# T01_Synth_Glove_v4.net
KiCad netlist of a schematic drawn in EAGLE
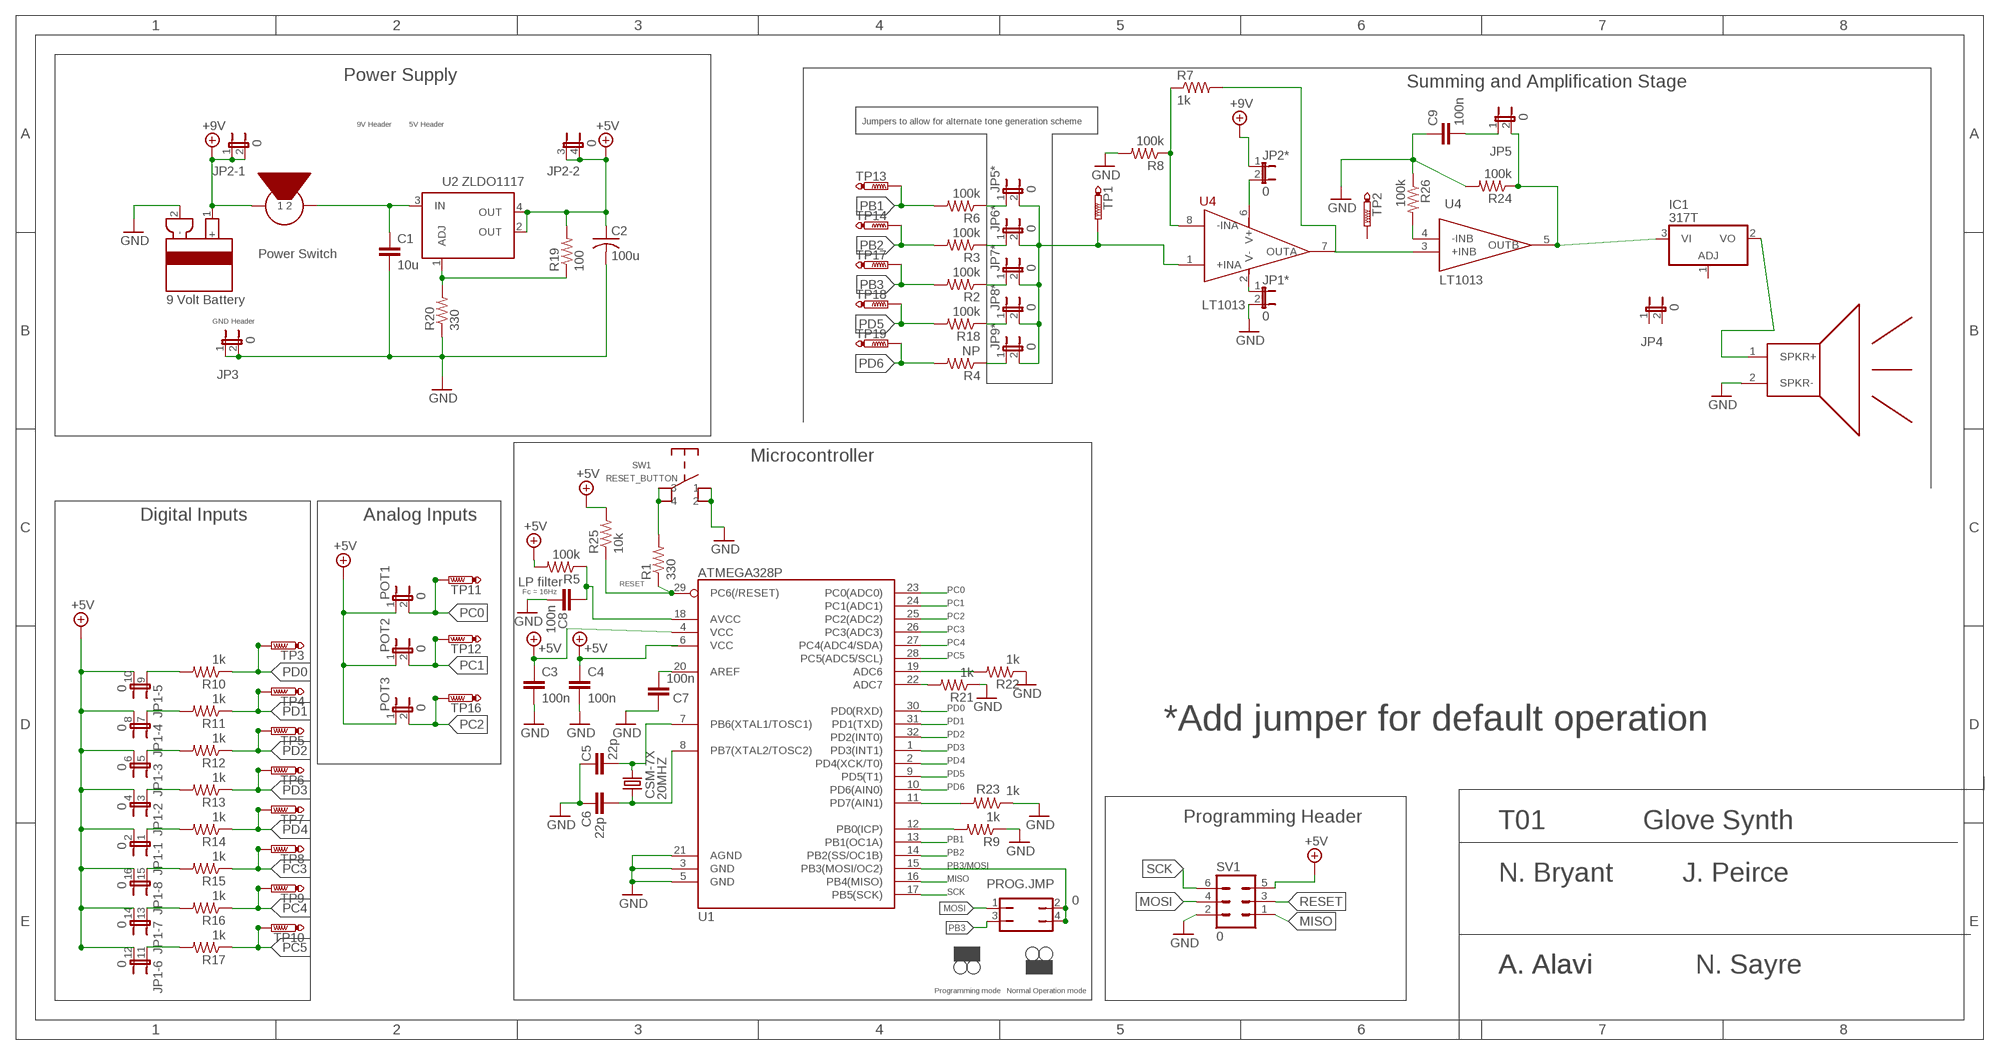
[diagram p0: schematic, sheet 1]

(export (version "E")
  (design (tool "Eeschema 10.0.6"))
  (components
    (comp (ref "20MHZ")
      (value "CSM-7X")
      (footprint "eagle-import:CSM-7X-DU")
      (libsource (lib "eagle-import") (part "CSM-7X-DU"))
    )
    (comp (ref "C1")
      (value "10u")
      (footprint "eagle-import:0603-CAP")
      (libsource (lib "eagle-import") (part "CAP0603-CAP"))
    )
    (comp (ref "C2")
      (value "100u")
      (footprint "eagle-import:C075-042X103")
      (libsource (lib "eagle-import") (part "C-US075-042X103"))
    )
    (comp (ref "C3")
      (value "100n")
      (footprint "eagle-import:0603-CAP")
      (libsource (lib "eagle-import") (part "CAP0603-CAP"))
    )
    (comp (ref "C4")
      (value "100n")
      (footprint "eagle-import:0603-CAP")
      (libsource (lib "eagle-import") (part "CAP0603-CAP"))
    )
    (comp (ref "C5")
      (value "22p")
      (footprint "eagle-import:0603-CAP")
      (libsource (lib "eagle-import") (part "CAP0603-CAP"))
    )
    (comp (ref "C6")
      (value "22p")
      (footprint "eagle-import:0603-CAP")
      (libsource (lib "eagle-import") (part "CAP0603-CAP"))
    )
    (comp (ref "C7")
      (value "100n")
      (footprint "eagle-import:0603-CAP")
      (libsource (lib "eagle-import") (part "CAP0603-CAP"))
    )
    (comp (ref "C8")
      (value "100n")
      (footprint "eagle-import:0603-CAP")
      (libsource (lib "eagle-import") (part "CAP0603-CAP"))
    )
    (comp (ref "C9")
      (value "100n")
      (footprint "eagle-import:0603-CAP")
      (libsource (lib "eagle-import") (part "CAP0603-CAP"))
    )
    (comp (ref "IC1")
      (value "317T")
      (footprint "eagle-import:TO220H")
      (libsource (lib "eagle-import") (part "317T"))
    )
    (comp (ref "JP1")
      (value "0")
      (footprint "eagle-import:JP8Q")
      (libsource (lib "eagle-import") (part "JP8QE"))
    )
    (comp (ref "JP1*")
      (value "0")
      (footprint "eagle-import:JP1")
      (libsource (lib "eagle-import") (part "JP1E"))
    )
    (comp (ref "JP2")
      (value "0")
      (footprint "eagle-import:JP2Q")
      (libsource (lib "eagle-import") (part "JP2QE"))
    )
    (comp (ref "JP2*")
      (value "0")
      (footprint "eagle-import:JP1")
      (libsource (lib "eagle-import") (part "JP1E"))
    )
    (comp (ref "JP3")
      (value "0")
      (footprint "eagle-import:JP1")
      (libsource (lib "eagle-import") (part "JP1E"))
    )
    (comp (ref "JP4")
      (value "0")
      (footprint "eagle-import:JP1")
      (libsource (lib "eagle-import") (part "JP1E"))
    )
    (comp (ref "JP5")
      (value "0")
      (footprint "eagle-import:JP1")
      (libsource (lib "eagle-import") (part "JP1E"))
    )
    (comp (ref "JP5*")
      (value "0")
      (footprint "eagle-import:JP1")
      (libsource (lib "eagle-import") (part "JP1E"))
    )
    (comp (ref "JP6*")
      (value "0")
      (footprint "eagle-import:JP1")
      (libsource (lib "eagle-import") (part "JP1E"))
    )
    (comp (ref "JP7*")
      (value "0")
      (footprint "eagle-import:JP1")
      (libsource (lib "eagle-import") (part "JP1E"))
    )
    (comp (ref "JP8*")
      (value "0")
      (footprint "eagle-import:JP1")
      (libsource (lib "eagle-import") (part "JP1E"))
    )
    (comp (ref "JP9*")
      (value "0")
      (footprint "eagle-import:JP1")
      (libsource (lib "eagle-import") (part "JP1E"))
    )
    (comp (ref "POT1")
      (value "0")
      (footprint "eagle-import:JP1")
      (libsource (lib "eagle-import") (part "JP1E"))
    )
    (comp (ref "POT2")
      (value "0")
      (footprint "eagle-import:JP1")
      (libsource (lib "eagle-import") (part "JP1E"))
    )
    (comp (ref "POT3")
      (value "0")
      (footprint "eagle-import:JP1")
      (libsource (lib "eagle-import") (part "JP1E"))
    )
    (comp (ref "PROG.JMP")
      (value "0")
      (footprint "eagle-import:JP2Q")
      (libsource (lib "eagle-import") (part "JP2Q"))
    )
    (comp (ref "R1")
      (value "330")
      (footprint "eagle-import:0603-RES")
      (libsource (lib "eagle-import") (part "RESISTOR0603"))
    )
    (comp (ref "R2")
      (value "100k")
      (footprint "eagle-import:0603-RES")
      (libsource (lib "eagle-import") (part "RESISTOR0603"))
    )
    (comp (ref "R3")
      (value "100k")
      (footprint "eagle-import:0603-RES")
      (libsource (lib "eagle-import") (part "RESISTOR0603"))
    )
    (comp (ref "R4")
      (value "NP")
      (footprint "eagle-import:0603-RES")
      (libsource (lib "eagle-import") (part "RESISTOR0603"))
    )
    (comp (ref "R5")
      (value "100k")
      (footprint "eagle-import:0603-RES")
      (libsource (lib "eagle-import") (part "RESISTOR0603"))
    )
    (comp (ref "R6")
      (value "100k")
      (footprint "eagle-import:0603-RES")
      (libsource (lib "eagle-import") (part "RESISTOR0603"))
    )
    (comp (ref "R7")
      (value "1k")
      (footprint "eagle-import:0603-RES")
      (libsource (lib "eagle-import") (part "RESISTOR0603"))
    )
    (comp (ref "R8")
      (value "100k")
      (footprint "eagle-import:0603-RES")
      (libsource (lib "eagle-import") (part "RESISTOR0603"))
    )
    (comp (ref "R9")
      (value "1k")
      (footprint "eagle-import:0603-RES")
      (libsource (lib "eagle-import") (part "RESISTOR0603"))
    )
    (comp (ref "R10")
      (value "1k")
      (footprint "eagle-import:0603-RES")
      (libsource (lib "eagle-import") (part "RESISTOR0603"))
    )
    (comp (ref "R11")
      (value "1k")
      (footprint "eagle-import:0603-RES")
      (libsource (lib "eagle-import") (part "RESISTOR0603"))
    )
    (comp (ref "R12")
      (value "1k")
      (footprint "eagle-import:0603-RES")
      (libsource (lib "eagle-import") (part "RESISTOR0603"))
    )
    (comp (ref "R13")
      (value "1k")
      (footprint "eagle-import:0603-RES")
      (libsource (lib "eagle-import") (part "RESISTOR0603"))
    )
    (comp (ref "R14")
      (value "1k")
      (footprint "eagle-import:0603-RES")
      (libsource (lib "eagle-import") (part "RESISTOR0603"))
    )
    (comp (ref "R15")
      (value "1k")
      (footprint "eagle-import:0603-RES")
      (libsource (lib "eagle-import") (part "RESISTOR0603"))
    )
    (comp (ref "R16")
      (value "1k")
      (footprint "eagle-import:0603-RES")
      (libsource (lib "eagle-import") (part "RESISTOR0603"))
    )
    (comp (ref "R17")
      (value "1k")
      (footprint "eagle-import:0603-RES")
      (libsource (lib "eagle-import") (part "RESISTOR0603"))
    )
    (comp (ref "R18")
      (value "100k")
      (footprint "eagle-import:0603-RES")
      (libsource (lib "eagle-import") (part "RESISTOR0603"))
    )
    (comp (ref "R19")
      (value "100")
      (footprint "eagle-import:0603-RES")
      (libsource (lib "eagle-import") (part "RESISTOR0603"))
    )
    (comp (ref "R20")
      (value "330")
      (footprint "eagle-import:0603-RES")
      (libsource (lib "eagle-import") (part "RESISTOR0603"))
    )
    (comp (ref "R21")
      (value "1k")
      (footprint "eagle-import:0603-RES")
      (libsource (lib "eagle-import") (part "RESISTOR0603"))
    )
    (comp (ref "R22")
      (value "1k")
      (footprint "eagle-import:0603-RES")
      (libsource (lib "eagle-import") (part "RESISTOR0603"))
    )
    (comp (ref "R23")
      (value "1k")
      (footprint "eagle-import:0603-RES")
      (libsource (lib "eagle-import") (part "RESISTOR0603"))
    )
    (comp (ref "R24")
      (value "100k")
      (footprint "eagle-import:0603-RES")
      (libsource (lib "eagle-import") (part "RESISTOR0603"))
    )
    (comp (ref "R25")
      (value "10k")
      (footprint "eagle-import:0603-RES")
      (libsource (lib "eagle-import") (part "RESISTOR0603"))
    )
    (comp (ref "R26")
      (value "100k")
      (footprint "eagle-import:0603-RES")
      (libsource (lib "eagle-import") (part "RESISTOR0603"))
    )
    (comp (ref "SV1")
      (value "0")
      (footprint "eagle-import:MA03-2")
      (libsource (lib "eagle-import") (part "MA03-2"))
    )
    (comp (ref "SW1")
      (value "RESET_BUTTON")
      (footprint "eagle-import:RESET_BUTTON")
      (libsource (lib "eagle-import") (part "RESET_BUTTON"))
    )
    (comp (ref "TP1")
      (value "PTR1B2,54")
      (footprint "eagle-import:B2,54")
      (libsource (lib "eagle-import") (part "PTR1B2,54"))
    )
    (comp (ref "TP2")
      (value "PTR1B2,54")
      (footprint "eagle-import:B2,54")
      (libsource (lib "eagle-import") (part "PTR1B2,54"))
    )
    (comp (ref "TP3")
      (value "PTR1B2,54")
      (footprint "eagle-import:B2,54")
      (libsource (lib "eagle-import") (part "PTR1B2,54"))
    )
    (comp (ref "TP4")
      (value "PTR1B2,54")
      (footprint "eagle-import:B2,54")
      (libsource (lib "eagle-import") (part "PTR1B2,54"))
    )
    (comp (ref "TP5")
      (value "PTR1B2,54")
      (footprint "eagle-import:B2,54")
      (libsource (lib "eagle-import") (part "PTR1B2,54"))
    )
    (comp (ref "TP6")
      (value "PTR1B2,54")
      (footprint "eagle-import:B2,54")
      (libsource (lib "eagle-import") (part "PTR1B2,54"))
    )
    (comp (ref "TP7")
      (value "PTR1B2,54")
      (footprint "eagle-import:B2,54")
      (libsource (lib "eagle-import") (part "PTR1B2,54"))
    )
    (comp (ref "TP8")
      (value "PTR1B2,54")
      (footprint "eagle-import:B2,54")
      (libsource (lib "eagle-import") (part "PTR1B2,54"))
    )
    (comp (ref "TP9")
      (value "PTR1B2,54")
      (footprint "eagle-import:B2,54")
      (libsource (lib "eagle-import") (part "PTR1B2,54"))
    )
    (comp (ref "TP10")
      (value "PTR1B2,54")
      (footprint "eagle-import:B2,54")
      (libsource (lib "eagle-import") (part "PTR1B2,54"))
    )
    (comp (ref "TP11")
      (value "PTR1B2,54")
      (footprint "eagle-import:B2,54")
      (libsource (lib "eagle-import") (part "PTR1B2,54"))
    )
    (comp (ref "TP12")
      (value "PTR1B2,54")
      (footprint "eagle-import:B2,54")
      (libsource (lib "eagle-import") (part "PTR1B2,54"))
    )
    (comp (ref "TP13")
      (value "PTR1B2,54")
      (footprint "eagle-import:B2,54")
      (libsource (lib "eagle-import") (part "PTR1B2,54"))
    )
    (comp (ref "TP14")
      (value "PTR1B2,54")
      (footprint "eagle-import:B2,54")
      (libsource (lib "eagle-import") (part "PTR1B2,54"))
    )
    (comp (ref "TP16")
      (value "PTR1B2,54")
      (footprint "eagle-import:B2,54")
      (libsource (lib "eagle-import") (part "PTR1B2,54"))
    )
    (comp (ref "TP17")
      (value "PTR1B2,54")
      (footprint "eagle-import:B2,54")
      (libsource (lib "eagle-import") (part "PTR1B2,54"))
    )
    (comp (ref "TP18")
      (value "PTR1B2,54")
      (footprint "eagle-import:B2,54")
      (libsource (lib "eagle-import") (part "PTR1B2,54"))
    )
    (comp (ref "TP19")
      (value "PTR1B2,54")
      (footprint "eagle-import:B2,54")
      (libsource (lib "eagle-import") (part "PTR1B2,54"))
    )
    (comp (ref "U$1")
      (value "SPEAKER")
      (footprint "eagle-import:JP1")
      (libsource (lib "eagle-import") (part "SPEAKER"))
    )
    (comp (ref "U$7")
      (value "POWER_SWITCH")
      (footprint "eagle-import:JP1")
      (libsource (lib "eagle-import") (part "POWER_SWITCH"))
    )
    (comp (ref "U$8")
      (value "9VOLTBATTERY")
      (footprint "eagle-import:JP1")
      (libsource (lib "eagle-import") (part "9VOLTBATTERY"))
    )
    (comp (ref "U1")
      (value "ATMEGA328P")
      (footprint "eagle-import:TQFP32-08")
      (libsource (lib "eagle-import") (part "ATMEGA328_SMT"))
    )
    (comp (ref "U2")
      (value "ZLDO1117")
      (footprint "eagle-import:SOT223")
      (libsource (lib "eagle-import") (part "ZLDO1117"))
    )
    (comp (ref "U4")
      (value "LT1013")
      (footprint "eagle-import:SO08")
      (libsource (lib "eagle-import") (part "LT1013"))
    )
  )
  (nets
    (net (code "1") (name "+5V") (class "Default")
      (node (ref "C2") (pin "1") (pinfunction "1_1") (pintype "passive"))
      (node (ref "C3") (pin "1") (pinfunction "1_1") (pintype "passive"))
      (node (ref "C4") (pin "1") (pinfunction "1_1") (pintype "passive"))
      (node (ref "JP1") (pin "10") (pinfunction "2_10") (pintype "passive"))
      (node (ref "JP1") (pin "12") (pinfunction "2_12") (pintype "passive"))
      (node (ref "JP1") (pin "14") (pinfunction "2_14") (pintype "passive"))
      (node (ref "JP1") (pin "16") (pinfunction "2_16") (pintype "passive"))
      (node (ref "JP1") (pin "2") (pinfunction "2_2") (pintype "passive"))
      (node (ref "JP1") (pin "4") (pinfunction "2_4") (pintype "passive"))
      (node (ref "JP1") (pin "6") (pinfunction "2_6") (pintype "passive"))
      (node (ref "JP1") (pin "8") (pinfunction "2_8") (pintype "passive"))
      (node (ref "JP2") (pin "3") (pinfunction "1_3") (pintype "passive"))
      (node (ref "JP2") (pin "4") (pinfunction "2_4") (pintype "passive"))
      (node (ref "POT1") (pin "1") (pinfunction "1_1") (pintype "passive"))
      (node (ref "POT2") (pin "1") (pinfunction "1_1") (pintype "passive"))
      (node (ref "POT3") (pin "1") (pinfunction "1_1") (pintype "passive"))
      (node (ref "R19") (pin "2") (pinfunction "2_2") (pintype "passive"))
      (node (ref "R25") (pin "2") (pinfunction "2_2") (pintype "passive"))
      (node (ref "R5") (pin "2") (pinfunction "2_2") (pintype "passive"))
      (node (ref "SV1") (pin "5") (pinfunction "5_5") (pintype "passive"))
      (node (ref "U1") (pin "4") (pinfunction "VCC_4") (pintype "bidirectional"))
      (node (ref "U2") (pin "2") (pinfunction "OUT_2") (pintype "bidirectional"))
      (node (ref "U2") (pin "4") (pinfunction "OUT_4") (pintype "bidirectional"))
    )
    (net (code "2") (name "+9V") (class "Default")
      (node (ref "JP2") (pin "1") (pinfunction "1_1") (pintype "passive"))
      (node (ref "JP2") (pin "2") (pinfunction "2_2") (pintype "passive"))
      (node (ref "JP2*") (pin "1") (pinfunction "1_1") (pintype "passive"))
      (node (ref "U$7") (pin "1") (pinfunction "1_1") (pintype "bidirectional"))
      (node (ref "U$8") (pin "1") (pinfunction "+_1") (pintype "bidirectional"))
    )
    (net (code "3") (name "/PB3{slash}MOSI") (class "Default")
      (node (ref "PROG.JMP") (pin "2") (pinfunction "2_2") (pintype "passive"))
      (node (ref "PROG.JMP") (pin "4") (pinfunction "4_4") (pintype "passive"))
      (node (ref "U1") (pin "15") (pinfunction "PB3(MOSI/OC2)_15") (pintype "bidirectional"))
    )
    (net (code "4") (name "GND") (class "Default")
      (node (ref "C1") (pin "2") (pinfunction "2_2") (pintype "passive"))
      (node (ref "C2") (pin "2") (pinfunction "2_2") (pintype "passive"))
      (node (ref "C3") (pin "2") (pinfunction "2_2") (pintype "passive"))
      (node (ref "C4") (pin "2") (pinfunction "2_2") (pintype "passive"))
      (node (ref "C5") (pin "2") (pinfunction "2_2") (pintype "passive"))
      (node (ref "C6") (pin "2") (pinfunction "2_2") (pintype "passive"))
      (node (ref "C7") (pin "2") (pinfunction "2_2") (pintype "passive"))
      (node (ref "C8") (pin "2") (pinfunction "2_2") (pintype "passive"))
      (node (ref "C9") (pin "1") (pinfunction "1_1") (pintype "passive"))
      (node (ref "JP1*") (pin "2") (pinfunction "2_2") (pintype "passive"))
      (node (ref "JP3") (pin "1") (pinfunction "1_1") (pintype "passive"))
      (node (ref "JP3") (pin "2") (pinfunction "2_2") (pintype "passive"))
      (node (ref "R20") (pin "1") (pinfunction "1_1") (pintype "passive"))
      (node (ref "R21") (pin "1") (pinfunction "1_1") (pintype "passive"))
      (node (ref "R22") (pin "1") (pinfunction "1_1") (pintype "passive"))
      (node (ref "R23") (pin "1") (pinfunction "1_1") (pintype "passive"))
      (node (ref "R24") (pin "2") (pinfunction "2_2") (pintype "passive"))
      (node (ref "R26") (pin "1") (pinfunction "1_1") (pintype "passive"))
      (node (ref "R8") (pin "2") (pinfunction "2_2") (pintype "passive"))
      (node (ref "R9") (pin "1") (pinfunction "1_1") (pintype "passive"))
      (node (ref "SV1") (pin "2") (pinfunction "2_2") (pintype "passive"))
      (node (ref "SW1") (pin "1") (pinfunction "1_1") (pintype "bidirectional"))
      (node (ref "SW1") (pin "2") (pinfunction "2_2") (pintype "bidirectional"))
      (node (ref "U$1") (pin "2") (pinfunction "SPKR-_2") (pintype "bidirectional"))
      (node (ref "U$8") (pin "2") (pinfunction "-_2") (pintype "bidirectional"))
      (node (ref "U1") (pin "21") (pinfunction "AGND_21") (pintype "bidirectional"))
      (node (ref "U1") (pin "3") (pinfunction "GND_3") (pintype "bidirectional"))
      (node (ref "U1") (pin "5") (pinfunction "GND_5") (pintype "bidirectional"))
    )
    (net (code "5") (name "MISO") (class "Default")
      (node (ref "SV1") (pin "1") (pinfunction "1_1") (pintype "passive"))
      (node (ref "U1") (pin "16") (pinfunction "PB4(MISO)_16") (pintype "bidirectional"))
    )
    (net (code "6") (name "MOSI") (class "Default")
      (node (ref "PROG.JMP") (pin "1") (pinfunction "1_1") (pintype "passive"))
      (node (ref "SV1") (pin "4") (pinfunction "4_4") (pintype "passive"))
    )
    (net (code "7") (name "Net-(C9-Pad2)") (class "Default")
      (node (ref "C9") (pin "2") (pinfunction "2_2") (pintype "passive"))
      (node (ref "JP5") (pin "1") (pinfunction "1_1") (pintype "passive"))
    )
    (net (code "8") (name "Net-(IC1-VI)") (class "Default")
      (node (ref "IC1") (pin "3") (pinfunction "VI_3") (pintype "input"))
      (node (ref "JP5") (pin "2") (pinfunction "2_2") (pintype "passive"))
      (node (ref "R24") (pin "1") (pinfunction "1_1") (pintype "passive"))
      (node (ref "U4") (pin "5") (pinfunction "OUTB_5") (pintype "bidirectional"))
    )
    (net (code "9") (name "Net-(JP1-Pad1)") (class "Default")
      (node (ref "JP1") (pin "1") (pinfunction "1_1") (pintype "passive"))
      (node (ref "R14") (pin "2") (pinfunction "2_2") (pintype "passive"))
    )
    (net (code "10") (name "Net-(JP1B-1)") (class "Default")
      (node (ref "JP1") (pin "3") (pinfunction "1_3") (pintype "passive"))
      (node (ref "R13") (pin "2") (pinfunction "2_2") (pintype "passive"))
    )
    (net (code "11") (name "Net-(JP1C-1)") (class "Default")
      (node (ref "JP1") (pin "5") (pinfunction "1_5") (pintype "passive"))
      (node (ref "R12") (pin "2") (pinfunction "2_2") (pintype "passive"))
    )
    (net (code "12") (name "Net-(JP1D-1)") (class "Default")
      (node (ref "JP1") (pin "7") (pinfunction "1_7") (pintype "passive"))
      (node (ref "R11") (pin "2") (pinfunction "2_2") (pintype "passive"))
    )
    (net (code "13") (name "Net-(JP1E-1)") (class "Default")
      (node (ref "JP1") (pin "9") (pinfunction "1_9") (pintype "passive"))
      (node (ref "R10") (pin "2") (pinfunction "2_2") (pintype "passive"))
    )
    (net (code "14") (name "Net-(JP1F-1)") (class "Default")
      (node (ref "JP1") (pin "11") (pinfunction "1_11") (pintype "passive"))
      (node (ref "R17") (pin "2") (pinfunction "2_2") (pintype "passive"))
    )
    (net (code "15") (name "Net-(JP1G-1)") (class "Default")
      (node (ref "JP1") (pin "13") (pinfunction "1_13") (pintype "passive"))
      (node (ref "R16") (pin "2") (pinfunction "2_2") (pintype "passive"))
    )
    (net (code "16") (name "Net-(JP1H-1)") (class "Default")
      (node (ref "JP1") (pin "15") (pinfunction "1_15") (pintype "passive"))
      (node (ref "R15") (pin "2") (pinfunction "2_2") (pintype "passive"))
    )
    (net (code "17") (name "Net-(JP5*-Pad1)") (class "Default")
      (node (ref "JP5*") (pin "1") (pinfunction "1_1") (pintype "passive"))
      (node (ref "R6") (pin "1") (pinfunction "1_1") (pintype "passive"))
    )
    (net (code "18") (name "Net-(JP6*-Pad1)") (class "Default")
      (node (ref "JP6*") (pin "1") (pinfunction "1_1") (pintype "passive"))
      (node (ref "R3") (pin "1") (pinfunction "1_1") (pintype "passive"))
    )
    (net (code "19") (name "Net-(JP7*-Pad1)") (class "Default")
      (node (ref "JP7*") (pin "1") (pinfunction "1_1") (pintype "passive"))
      (node (ref "R2") (pin "1") (pinfunction "1_1") (pintype "passive"))
    )
    (net (code "20") (name "Net-(JP8*-Pad1)") (class "Default")
      (node (ref "JP8*") (pin "1") (pinfunction "1_1") (pintype "passive"))
      (node (ref "R18") (pin "1") (pinfunction "1_1") (pintype "passive"))
    )
    (net (code "21") (name "Net-(JP9*-Pad1)") (class "Default")
      (node (ref "JP9*") (pin "1") (pinfunction "1_1") (pintype "passive"))
      (node (ref "R4") (pin "1") (pinfunction "1_1") (pintype "passive"))
    )
    (net (code "22") (name "Net-(R1-Pad2)") (class "Default")
      (node (ref "R1") (pin "2") (pinfunction "2_2") (pintype "passive"))
      (node (ref "SW1") (pin "3") (pinfunction "3_3") (pintype "bidirectional"))
      (node (ref "SW1") (pin "4") (pinfunction "4_4") (pintype "bidirectional"))
    )
    (net (code "23") (name "Net-(U1-ADC6)") (class "Default")
      (node (ref "R22") (pin "2") (pinfunction "2_2") (pintype "passive"))
      (node (ref "U1") (pin "19") (pinfunction "ADC6_19") (pintype "bidirectional"))
    )
    (net (code "24") (name "Net-(U1-ADC7)") (class "Default")
      (node (ref "R21") (pin "2") (pinfunction "2_2") (pintype "passive"))
      (node (ref "U1") (pin "22") (pinfunction "ADC7_22") (pintype "bidirectional"))
    )
    (net (code "25") (name "Net-(U1-AREF)") (class "Default")
      (node (ref "C7") (pin "1") (pinfunction "1_1") (pintype "passive"))
      (node (ref "U1") (pin "20") (pinfunction "AREF_20") (pintype "bidirectional"))
    )
    (net (code "26") (name "Net-(U1-AVCC)") (class "Default")
      (node (ref "C8") (pin "1") (pinfunction "1_1") (pintype "passive"))
      (node (ref "R5") (pin "1") (pinfunction "1_1") (pintype "passive"))
      (node (ref "U1") (pin "18") (pinfunction "AVCC_18") (pintype "bidirectional"))
    )
    (net (code "27") (name "Net-(U1-PB0(ICP))") (class "Default")
      (node (ref "R9") (pin "2") (pinfunction "2_2") (pintype "passive"))
      (node (ref "U1") (pin "12") (pinfunction "PB0(ICP)_12") (pintype "bidirectional"))
    )
    (net (code "28") (name "Net-(U1-PB6(XTAL1{slash}TOSC1))") (class "Default")
      (node (ref "20MHZ") (pin "1") (pinfunction "1_1") (pintype "passive"))
      (node (ref "C5") (pin "1") (pinfunction "1_1") (pintype "passive"))
      (node (ref "U1") (pin "7") (pinfunction "PB6(XTAL1/TOSC1)_7") (pintype "bidirectional"))
    )
    (net (code "29") (name "Net-(U1-PB7(XTAL2{slash}TOSC2))") (class "Default")
      (node (ref "20MHZ") (pin "2") (pinfunction "2_2") (pintype "passive"))
      (node (ref "C6") (pin "1") (pinfunction "1_1") (pintype "passive"))
      (node (ref "U1") (pin "8") (pinfunction "PB7(XTAL2/TOSC2)_8") (pintype "bidirectional"))
    )
    (net (code "30") (name "Net-(U1-PD7(AIN1))") (class "Default")
      (node (ref "R23") (pin "2") (pinfunction "2_2") (pintype "passive"))
      (node (ref "U1") (pin "11") (pinfunction "PD7(AIN1)_11") (pintype "bidirectional"))
    )
    (net (code "31") (name "Net-(U2-ADJ)") (class "Default")
      (node (ref "R19") (pin "1") (pinfunction "1_1") (pintype "passive"))
      (node (ref "R20") (pin "2") (pinfunction "2_2") (pintype "passive"))
      (node (ref "U2") (pin "1") (pinfunction "ADJ_1") (pintype "bidirectional"))
    )
    (net (code "32") (name "Net-(U2-IN)") (class "Default")
      (node (ref "C1") (pin "1") (pinfunction "1_1") (pintype "passive"))
      (node (ref "U$7") (pin "2") (pinfunction "2_2") (pintype "bidirectional"))
      (node (ref "U2") (pin "3") (pinfunction "IN_3") (pintype "bidirectional"))
    )
    (net (code "33") (name "Net-(U4-+INA)") (class "Default")
      (node (ref "JP5*") (pin "2") (pinfunction "2_2") (pintype "passive"))
      (node (ref "JP6*") (pin "2") (pinfunction "2_2") (pintype "passive"))
      (node (ref "JP7*") (pin "2") (pinfunction "2_2") (pintype "passive"))
      (node (ref "JP8*") (pin "2") (pinfunction "2_2") (pintype "passive"))
      (node (ref "JP9*") (pin "2") (pinfunction "2_2") (pintype "passive"))
      (node (ref "TP1") (pin "TP") (pinfunction "TP_TP") (pintype "input"))
      (node (ref "U4") (pin "1") (pinfunction "+INA_1") (pintype "bidirectional"))
    )
    (net (code "34") (name "Net-(U4--INA)") (class "Default")
      (node (ref "R7") (pin "1") (pinfunction "1_1") (pintype "passive"))
      (node (ref "R8") (pin "1") (pinfunction "1_1") (pintype "passive"))
      (node (ref "U4") (pin "8") (pinfunction "-INA_8") (pintype "bidirectional"))
    )
    (net (code "35") (name "Net-(U4--INB)") (class "Default")
      (node (ref "R26") (pin "2") (pinfunction "2_2") (pintype "passive"))
      (node (ref "U4") (pin "4") (pinfunction "-INB_4") (pintype "bidirectional"))
    )
    (net (code "36") (name "Net-(U4-OUTA)") (class "Default")
      (node (ref "R7") (pin "2") (pinfunction "2_2") (pintype "passive"))
      (node (ref "U4") (pin "7") (pinfunction "OUTA_7") (pintype "bidirectional"))
    )
    (net (code "37") (name "Net-(U4-V+)") (class "Default")
      (node (ref "JP2*") (pin "2") (pinfunction "2_2") (pintype "passive"))
      (node (ref "U4") (pin "6") (pinfunction "V+_6") (pintype "power_in"))
    )
    (net (code "38") (name "Net-(U4-V-)") (class "Default")
      (node (ref "JP1*") (pin "1") (pinfunction "1_1") (pintype "passive"))
      (node (ref "U4") (pin "2") (pinfunction "V-_2") (pintype "power_in"))
    )
    (net (code "39") (name "PB1") (class "Default")
      (node (ref "R6") (pin "2") (pinfunction "2_2") (pintype "passive"))
      (node (ref "TP13") (pin "TP") (pinfunction "TP_TP") (pintype "input"))
      (node (ref "U1") (pin "13") (pinfunction "PB1(OC1A)_13") (pintype "bidirectional"))
    )
    (net (code "40") (name "PB2") (class "Default")
      (node (ref "R3") (pin "2") (pinfunction "2_2") (pintype "passive"))
      (node (ref "TP14") (pin "TP") (pinfunction "TP_TP") (pintype "input"))
      (node (ref "U1") (pin "14") (pinfunction "PB2(SS/OC1B)_14") (pintype "bidirectional"))
    )
    (net (code "41") (name "PB3") (class "Default")
      (node (ref "PROG.JMP") (pin "3") (pinfunction "3_3") (pintype "passive"))
      (node (ref "R2") (pin "2") (pinfunction "2_2") (pintype "passive"))
      (node (ref "TP17") (pin "TP") (pinfunction "TP_TP") (pintype "input"))
    )
    (net (code "42") (name "PC0") (class "Default")
      (node (ref "POT1") (pin "2") (pinfunction "2_2") (pintype "passive"))
      (node (ref "TP11") (pin "TP") (pinfunction "TP_TP") (pintype "input"))
      (node (ref "U1") (pin "23") (pinfunction "PC0(ADC0)_23") (pintype "bidirectional"))
    )
    (net (code "43") (name "PC1") (class "Default")
      (node (ref "POT2") (pin "2") (pinfunction "2_2") (pintype "passive"))
      (node (ref "TP12") (pin "TP") (pinfunction "TP_TP") (pintype "input"))
      (node (ref "U1") (pin "24") (pinfunction "PC1(ADC1)_24") (pintype "bidirectional"))
    )
    (net (code "44") (name "PC2") (class "Default")
      (node (ref "POT3") (pin "2") (pinfunction "2_2") (pintype "passive"))
      (node (ref "TP16") (pin "TP") (pinfunction "TP_TP") (pintype "input"))
      (node (ref "U1") (pin "25") (pinfunction "PC2(ADC2)_25") (pintype "bidirectional"))
    )
    (net (code "45") (name "PC3") (class "Default")
      (node (ref "R15") (pin "1") (pinfunction "1_1") (pintype "passive"))
      (node (ref "TP8") (pin "TP") (pinfunction "TP_TP") (pintype "input"))
      (node (ref "U1") (pin "26") (pinfunction "PC3(ADC3)_26") (pintype "bidirectional"))
    )
    (net (code "46") (name "PC4") (class "Default")
      (node (ref "R16") (pin "1") (pinfunction "1_1") (pintype "passive"))
      (node (ref "TP9") (pin "TP") (pinfunction "TP_TP") (pintype "input"))
      (node (ref "U1") (pin "27") (pinfunction "PC4(ADC4/SDA)_27") (pintype "bidirectional"))
    )
    (net (code "47") (name "PC5") (class "Default")
      (node (ref "R17") (pin "1") (pinfunction "1_1") (pintype "passive"))
      (node (ref "TP10") (pin "TP") (pinfunction "TP_TP") (pintype "input"))
      (node (ref "U1") (pin "28") (pinfunction "PC5(ADC5/SCL)_28") (pintype "bidirectional"))
    )
    (net (code "48") (name "PD0") (class "Default")
      (node (ref "R10") (pin "1") (pinfunction "1_1") (pintype "passive"))
      (node (ref "TP3") (pin "TP") (pinfunction "TP_TP") (pintype "input"))
      (node (ref "U1") (pin "30") (pinfunction "PD0(RXD)_30") (pintype "bidirectional"))
    )
    (net (code "49") (name "PD1") (class "Default")
      (node (ref "R11") (pin "1") (pinfunction "1_1") (pintype "passive"))
      (node (ref "TP4") (pin "TP") (pinfunction "TP_TP") (pintype "input"))
      (node (ref "U1") (pin "31") (pinfunction "PD1(TXD)_31") (pintype "bidirectional"))
    )
    (net (code "50") (name "PD2") (class "Default")
      (node (ref "R12") (pin "1") (pinfunction "1_1") (pintype "passive"))
      (node (ref "TP5") (pin "TP") (pinfunction "TP_TP") (pintype "input"))
      (node (ref "U1") (pin "32") (pinfunction "PD2(INT0)_32") (pintype "bidirectional"))
    )
    (net (code "51") (name "PD3") (class "Default")
      (node (ref "R13") (pin "1") (pinfunction "1_1") (pintype "passive"))
      (node (ref "TP6") (pin "TP") (pinfunction "TP_TP") (pintype "input"))
      (node (ref "U1") (pin "1") (pinfunction "PD3(INT1)_1") (pintype "bidirectional"))
    )
    (net (code "52") (name "PD4") (class "Default")
      (node (ref "R14") (pin "1") (pinfunction "1_1") (pintype "passive"))
      (node (ref "TP7") (pin "TP") (pinfunction "TP_TP") (pintype "input"))
      (node (ref "U1") (pin "2") (pinfunction "PD4(XCK/T0)_2") (pintype "bidirectional"))
    )
    (net (code "53") (name "PD5") (class "Default")
      (node (ref "R18") (pin "2") (pinfunction "2_2") (pintype "passive"))
      (node (ref "TP18") (pin "TP") (pinfunction "TP_TP") (pintype "input"))
      (node (ref "U1") (pin "9") (pinfunction "PD5(T1)_9") (pintype "bidirectional"))
    )
    (net (code "54") (name "PD6") (class "Default")
      (node (ref "R4") (pin "2") (pinfunction "2_2") (pintype "passive"))
      (node (ref "TP19") (pin "TP") (pinfunction "TP_TP") (pintype "input"))
      (node (ref "U1") (pin "10") (pinfunction "PD6(AIN0)_10") (pintype "bidirectional"))
    )
    (net (code "55") (name "RESET") (class "Default")
      (node (ref "R1") (pin "1") (pinfunction "1_1") (pintype "passive"))
      (node (ref "R25") (pin "1") (pinfunction "1_1") (pintype "passive"))
      (node (ref "SV1") (pin "3") (pinfunction "3_3") (pintype "passive"))
      (node (ref "U1") (pin "29") (pinfunction "PC6(/RESET)_29") (pintype "bidirectional"))
    )
    (net (code "56") (name "SCK") (class "Default")
      (node (ref "SV1") (pin "6") (pinfunction "6_6") (pintype "passive"))
      (node (ref "U1") (pin "17") (pinfunction "PB5(SCK)_17") (pintype "bidirectional"))
    )
    (net (code "57") (name "unconnected-(IC1-ADJ-Pad1)") (class "Default")
      (node (ref "IC1") (pin "1") (pinfunction "ADJ_1") (pintype "input"))
    )
    (net (code "58") (name "unconnected-(IC1-VO-Pad2)") (class "Default")
      (node (ref "IC1") (pin "2") (pinfunction "VO_2") (pintype "passive"))
    )
    (net (code "59") (name "unconnected-(JP4-Pad1)") (class "Default")
      (node (ref "JP4") (pin "1") (pinfunction "1_1") (pintype "passive"))
    )
    (net (code "60") (name "unconnected-(JP4-Pad2)") (class "Default")
      (node (ref "JP4") (pin "2") (pinfunction "2_2") (pintype "passive"))
    )
    (net (code "61") (name "unconnected-(TP2-PadTP)") (class "Default")
      (node (ref "TP2") (pin "TP") (pinfunction "TP_TP") (pintype "input"))
    )
    (net (code "62") (name "unconnected-(U$1-SPKR+-Pad1)") (class "Default")
      (node (ref "U$1") (pin "1") (pinfunction "SPKR+_1") (pintype "bidirectional"))
    )
    (net (code "63") (name "unconnected-(U1-VCC-Pad6)") (class "Default")
      (node (ref "U1") (pin "6") (pinfunction "VCC_6") (pintype "bidirectional"))
    )
    (net (code "64") (name "unconnected-(U4-+INB-Pad3)") (class "Default")
      (node (ref "U4") (pin "3") (pinfunction "+INB_3") (pintype "bidirectional"))
    )
  )
)
